# Qwiic_Button-1b.net
KiCad netlist of a schematic drawn in EAGLE
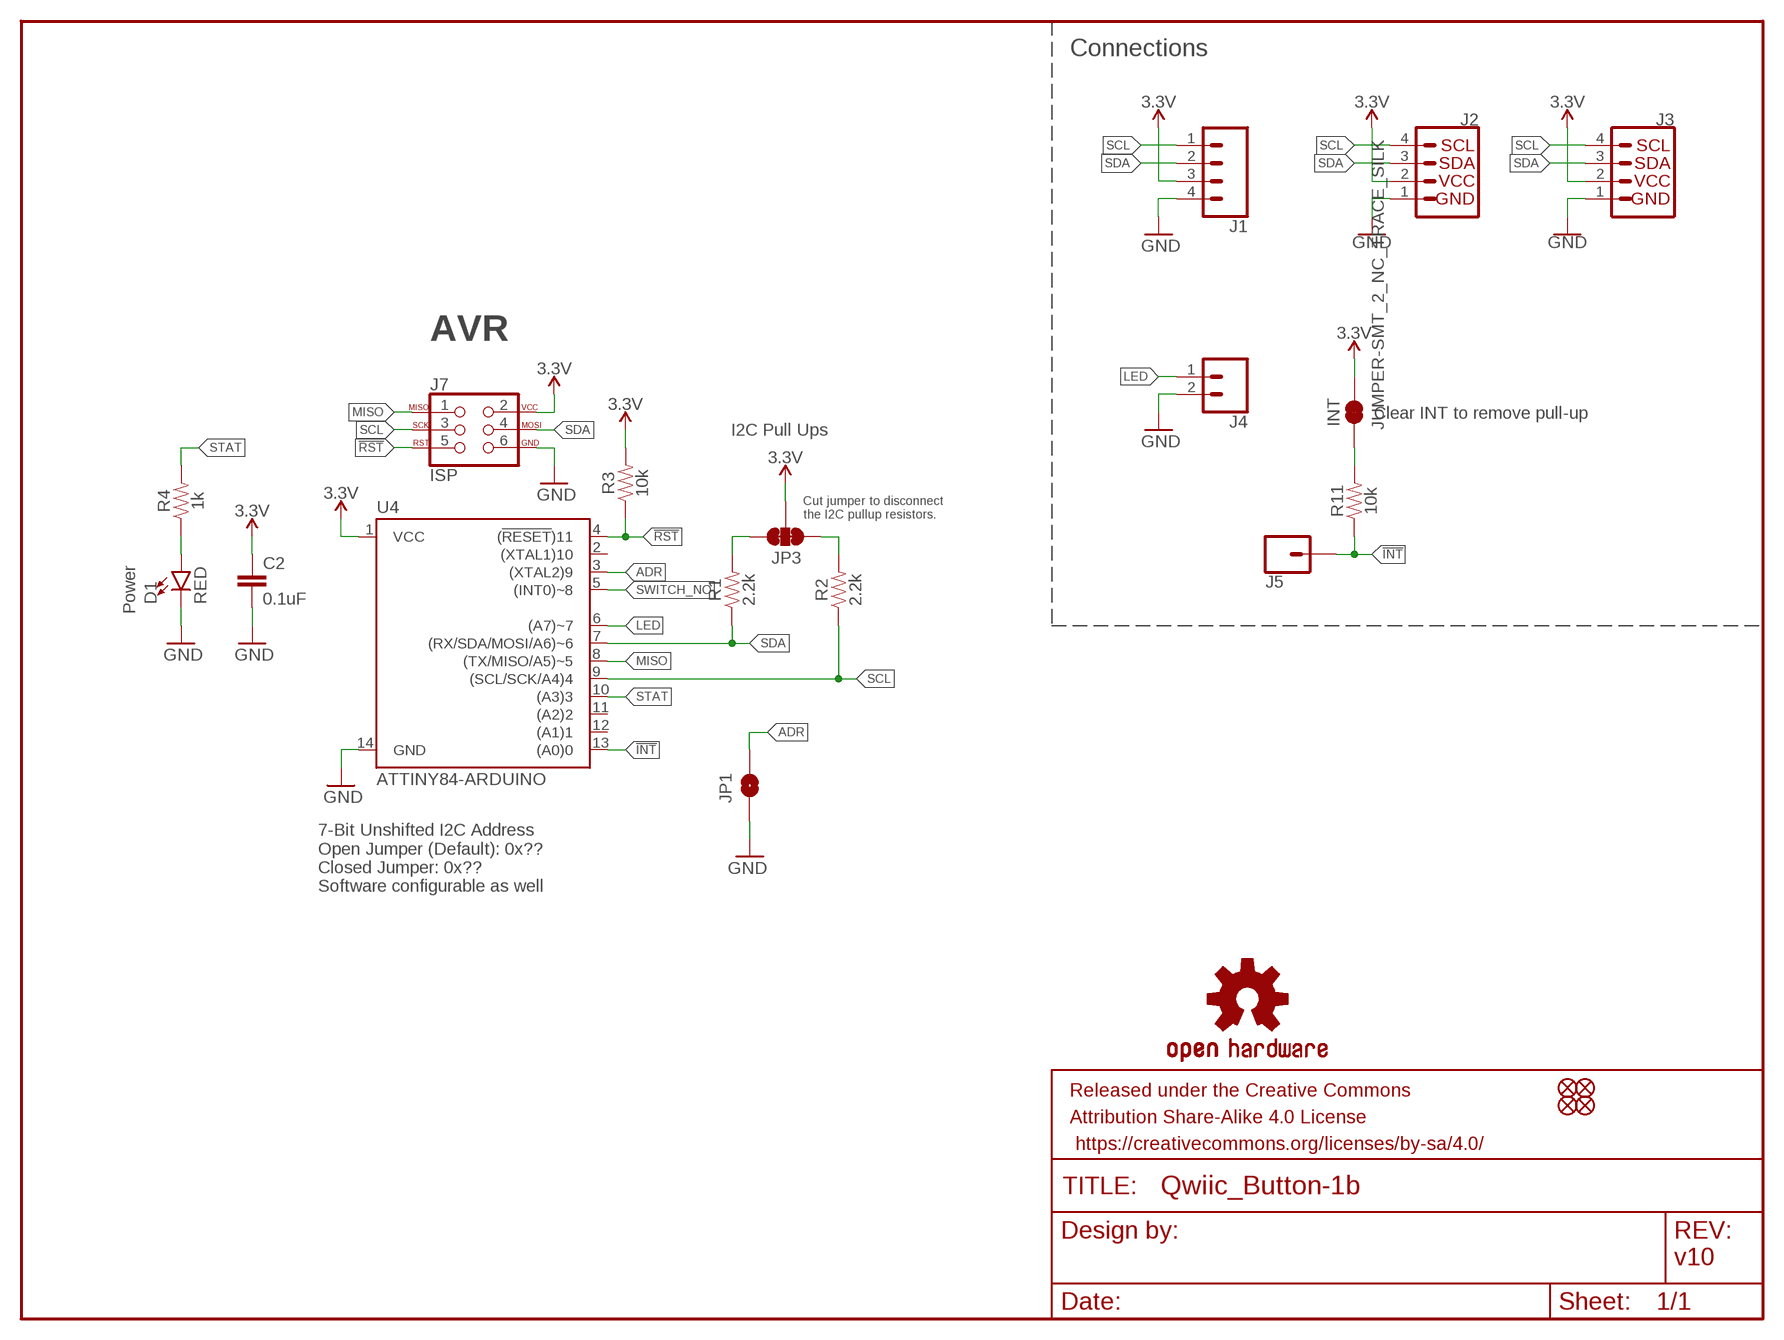
[diagram p0: schematic, sheet 1]

(export (version "E")
  (design (tool "Eeschema 10.0.6"))
  (components
    (comp (ref "C2")
      (value "0.1uF")
      (footprint "eagle-import:0603")
      (libsource (lib "eagle-import") (part "0.1UF-0603-25V-(+80/-20%)"))
    )
    (comp (ref "D1")
      (value "RED")
      (footprint "eagle-import:LED-0603")
      (libsource (lib "eagle-import") (part "LED-RED0603"))
    )
    (comp (ref "FRAME1")
      (value "FRAME-LETTER")
      (footprint "eagle-import:CREATIVE_COMMONS")
      (libsource (lib "eagle-import") (part "FRAME-LETTER"))
    )
    (comp (ref "INT")
      (value "JUMPER-SMT_2_NC_TRACE_SILK")
      (footprint "eagle-import:SMT-JUMPER_2_NC_TRACE_SILK")
      (libsource (lib "eagle-import") (part "JUMPER-SMT_2_NC_TRACE_SILK"))
    )
    (comp (ref "J1")
      (value "CONN_041X04_NO_SILK")
      (footprint "eagle-import:1X04_NO_SILK")
      (libsource (lib "eagle-import") (part "CONN_041X04_NO_SILK"))
    )
    (comp (ref "J2")
      (value "QWIIC_CONNECTORJS-1MM")
      (footprint "eagle-import:JST04_1MM_RA")
      (libsource (lib "eagle-import") (part "QWIIC_CONNECTORJS-1MM"))
    )
    (comp (ref "J3")
      (value "QWIIC_CONNECTORJS-1MM")
      (footprint "eagle-import:JST04_1MM_RA")
      (libsource (lib "eagle-import") (part "QWIIC_CONNECTORJS-1MM"))
    )
    (comp (ref "J4")
      (value "CONN_021X02_NO_SILK")
      (footprint "eagle-import:1X02_NO_SILK")
      (libsource (lib "eagle-import") (part "CONN_021X02_NO_SILK"))
    )
    (comp (ref "J5")
      (value "CONN_01PTH_NO_SILK_YES_STOP")
      (footprint "eagle-import:1X01_NO_SILK")
      (libsource (lib "eagle-import") (part "CONN_01PTH_NO_SILK_YES_STOP"))
    )
    (comp (ref "J7")
      (value "ISP")
      (footprint "eagle-import:2X3_TEST_POINTS")
      (libsource (lib "eagle-import") (part "AVR_SPI_PROG_3X2TESTPOINTS"))
    )
    (comp (ref "JP1")
      (value "JUMPER-SMT_2_NO_SILK")
      (footprint "eagle-import:SMT-JUMPER_2_NO_SILK")
      (libsource (lib "eagle-import") (part "JUMPER-SMT_2_NO_SILK"))
    )
    (comp (ref "JP2")
      (value "FIDUCIALUFIDUCIAL")
      (footprint "eagle-import:MICRO-FIDUCIAL")
      (libsource (lib "eagle-import") (part "FIDUCIALUFIDUCIAL"))
    )
    (comp (ref "JP3")
      (value "JUMPER-SMT_3_2-NC_TRACE_SILK")
      (footprint "eagle-import:SMT-JUMPER_3_2-NC_TRACE_SILK")
      (libsource (lib "eagle-import") (part "JUMPER-SMT_3_2-NC_TRACE_SILK"))
    )
    (comp (ref "JP6")
      (value "FIDUCIALUFIDUCIAL")
      (footprint "eagle-import:MICRO-FIDUCIAL")
      (libsource (lib "eagle-import") (part "FIDUCIALUFIDUCIAL"))
    )
    (comp (ref "JP8")
      (value "FIDUCIALUFIDUCIAL")
      (footprint "eagle-import:MICRO-FIDUCIAL")
      (libsource (lib "eagle-import") (part "FIDUCIALUFIDUCIAL"))
    )
    (comp (ref "JP9")
      (value "FIDUCIALUFIDUCIAL")
      (footprint "eagle-import:MICRO-FIDUCIAL")
      (libsource (lib "eagle-import") (part "FIDUCIALUFIDUCIAL"))
    )
    (comp (ref "LOGO1")
      (value "OSHW-LOGOMINI")
      (footprint "eagle-import:OSHW-LOGO-MINI")
      (libsource (lib "eagle-import") (part "OSHW-LOGOMINI"))
    )
    (comp (ref "R1")
      (value "2.2k")
      (footprint "eagle-import:0603")
      (libsource (lib "eagle-import") (part "2.2KOHM-0603-1/10W-1%"))
    )
    (comp (ref "R2")
      (value "2.2k")
      (footprint "eagle-import:0603")
      (libsource (lib "eagle-import") (part "2.2KOHM-0603-1/10W-1%"))
    )
    (comp (ref "R3")
      (value "10k")
      (footprint "eagle-import:0603")
      (libsource (lib "eagle-import") (part "10KOHM-0603-1/10W-1%"))
    )
    (comp (ref "R4")
      (value "1k")
      (footprint "eagle-import:0603")
      (libsource (lib "eagle-import") (part "1KOHM-0603-1/10W-1%"))
    )
    (comp (ref "R11")
      (value "10k")
      (footprint "eagle-import:0603")
      (libsource (lib "eagle-import") (part "10KOHM-0603-1/10W-1%"))
    )
    (comp (ref "U4")
      (value "ATTINY84-ARDUINO")
      (footprint "eagle-import:SO14")
      (libsource (lib "eagle-import") (part "ATTINY84-ARDUINO"))
    )
  )
  (nets
    (net (code "1") (name "/~{INT}") (class "Default")
      (node (ref "J5") (pin "1") (pinfunction "1_1") (pintype "passive"))
      (node (ref "R11") (pin "1") (pinfunction "1_1") (pintype "passive"))
      (node (ref "U4") (pin "13") (pinfunction "(A0)0_13") (pintype "bidirectional"))
    )
    (net (code "2") (name "/~{RST}") (class "Default")
      (node (ref "J7") (pin "5") (pinfunction "5_5") (pintype "passive"))
      (node (ref "R3") (pin "1") (pinfunction "1_1") (pintype "passive"))
      (node (ref "U4") (pin "4") (pinfunction "(~{RESET})11_4") (pintype "bidirectional"))
    )
    (net (code "3") (name "3.3V") (class "Default")
      (node (ref "C2") (pin "1") (pinfunction "1_1") (pintype "passive"))
      (node (ref "INT") (pin "2") (pinfunction "2_2") (pintype "passive"))
      (node (ref "J1") (pin "3") (pinfunction "3_3") (pintype "passive"))
      (node (ref "J2") (pin "2") (pinfunction "2_2") (pintype "power_in"))
      (node (ref "J3") (pin "2") (pinfunction "2_2") (pintype "power_in"))
      (node (ref "J7") (pin "2") (pinfunction "2_2") (pintype "passive"))
      (node (ref "JP3") (pin "2") (pinfunction "2_2") (pintype "passive"))
      (node (ref "R3") (pin "2") (pinfunction "2_2") (pintype "passive"))
      (node (ref "U4") (pin "1") (pinfunction "VCC_1") (pintype "bidirectional"))
    )
    (net (code "4") (name "ADR") (class "Default")
      (node (ref "JP1") (pin "2") (pinfunction "2_2") (pintype "passive"))
      (node (ref "U4") (pin "3") (pinfunction "(XTAL2)9_3") (pintype "bidirectional"))
    )
    (net (code "5") (name "GND") (class "Default")
      (node (ref "C2") (pin "2") (pinfunction "2_2") (pintype "passive"))
      (node (ref "D1") (pin "C") (pinfunction "C_C") (pintype "passive"))
      (node (ref "J1") (pin "4") (pinfunction "4_4") (pintype "passive"))
      (node (ref "J2") (pin "1") (pinfunction "1_1") (pintype "power_in"))
      (node (ref "J3") (pin "1") (pinfunction "1_1") (pintype "power_in"))
      (node (ref "J4") (pin "2") (pinfunction "2_2") (pintype "passive"))
      (node (ref "J7") (pin "6") (pinfunction "6_6") (pintype "passive"))
      (node (ref "JP1") (pin "1") (pinfunction "1_1") (pintype "passive"))
      (node (ref "U4") (pin "14") (pinfunction "GND_14") (pintype "bidirectional"))
    )
    (net (code "6") (name "LED") (class "Default")
      (node (ref "J4") (pin "1") (pinfunction "1_1") (pintype "passive"))
      (node (ref "U4") (pin "6") (pinfunction "(A7)~{7}_6") (pintype "bidirectional"))
    )
    (net (code "7") (name "MISO") (class "Default")
      (node (ref "J7") (pin "1") (pinfunction "1_1") (pintype "passive"))
      (node (ref "U4") (pin "8") (pinfunction "(TX/MISO/A5)~{5}_8") (pintype "bidirectional"))
    )
    (net (code "8") (name "Net-(D1-PadA)") (class "Default")
      (node (ref "D1") (pin "A") (pinfunction "A_A") (pintype "passive"))
      (node (ref "R4") (pin "1") (pinfunction "1_1") (pintype "passive"))
    )
    (net (code "9") (name "Net-(INT-Pad1)") (class "Default")
      (node (ref "INT") (pin "1") (pinfunction "1_1") (pintype "passive"))
      (node (ref "R11") (pin "2") (pinfunction "2_2") (pintype "passive"))
    )
    (net (code "10") (name "Net-(JP3-Pad1)") (class "Default")
      (node (ref "JP3") (pin "1") (pinfunction "1_1") (pintype "passive"))
      (node (ref "R2") (pin "2") (pinfunction "2_2") (pintype "passive"))
    )
    (net (code "11") (name "Net-(JP3-Pad3)") (class "Default")
      (node (ref "JP3") (pin "3") (pinfunction "3_3") (pintype "passive"))
      (node (ref "R1") (pin "2") (pinfunction "2_2") (pintype "passive"))
    )
    (net (code "12") (name "SCL") (class "Default")
      (node (ref "J1") (pin "1") (pinfunction "1_1") (pintype "passive"))
      (node (ref "J2") (pin "4") (pinfunction "4_4") (pintype "passive"))
      (node (ref "J3") (pin "4") (pinfunction "4_4") (pintype "passive"))
      (node (ref "J7") (pin "3") (pinfunction "3_3") (pintype "passive"))
      (node (ref "R2") (pin "1") (pinfunction "1_1") (pintype "passive"))
      (node (ref "U4") (pin "9") (pinfunction "(SCL/SCK/A4)4_9") (pintype "bidirectional"))
    )
    (net (code "13") (name "SDA") (class "Default")
      (node (ref "J1") (pin "2") (pinfunction "2_2") (pintype "passive"))
      (node (ref "J2") (pin "3") (pinfunction "3_3") (pintype "passive"))
      (node (ref "J3") (pin "3") (pinfunction "3_3") (pintype "passive"))
      (node (ref "J7") (pin "4") (pinfunction "4_4") (pintype "passive"))
      (node (ref "R1") (pin "1") (pinfunction "1_1") (pintype "passive"))
      (node (ref "U4") (pin "7") (pinfunction "(RX/SDA/MOSI/A6)~{6}_7") (pintype "bidirectional"))
    )
    (net (code "14") (name "STAT") (class "Default")
      (node (ref "R4") (pin "2") (pinfunction "2_2") (pintype "passive"))
      (node (ref "U4") (pin "10") (pinfunction "(A3)3_10") (pintype "bidirectional"))
    )
    (net (code "15") (name "SWITCH_NO") (class "Default")
      (node (ref "U4") (pin "5") (pinfunction "(INT0)~{8}_5") (pintype "bidirectional"))
    )
    (net (code "16") (name "unconnected-(U4-(A1)1-Pad12)") (class "Default")
      (node (ref "U4") (pin "12") (pinfunction "(A1)1_12") (pintype "bidirectional"))
    )
    (net (code "17") (name "unconnected-(U4-(A2)2-Pad11)") (class "Default")
      (node (ref "U4") (pin "11") (pinfunction "(A2)2_11") (pintype "bidirectional"))
    )
    (net (code "18") (name "unconnected-(U4-(XTAL1)10-Pad2)") (class "Default")
      (node (ref "U4") (pin "2") (pinfunction "(XTAL1)10_2") (pintype "bidirectional"))
    )
  )
)
